# arm.net
KiCad netlist of a schematic drawn in Altium Designer
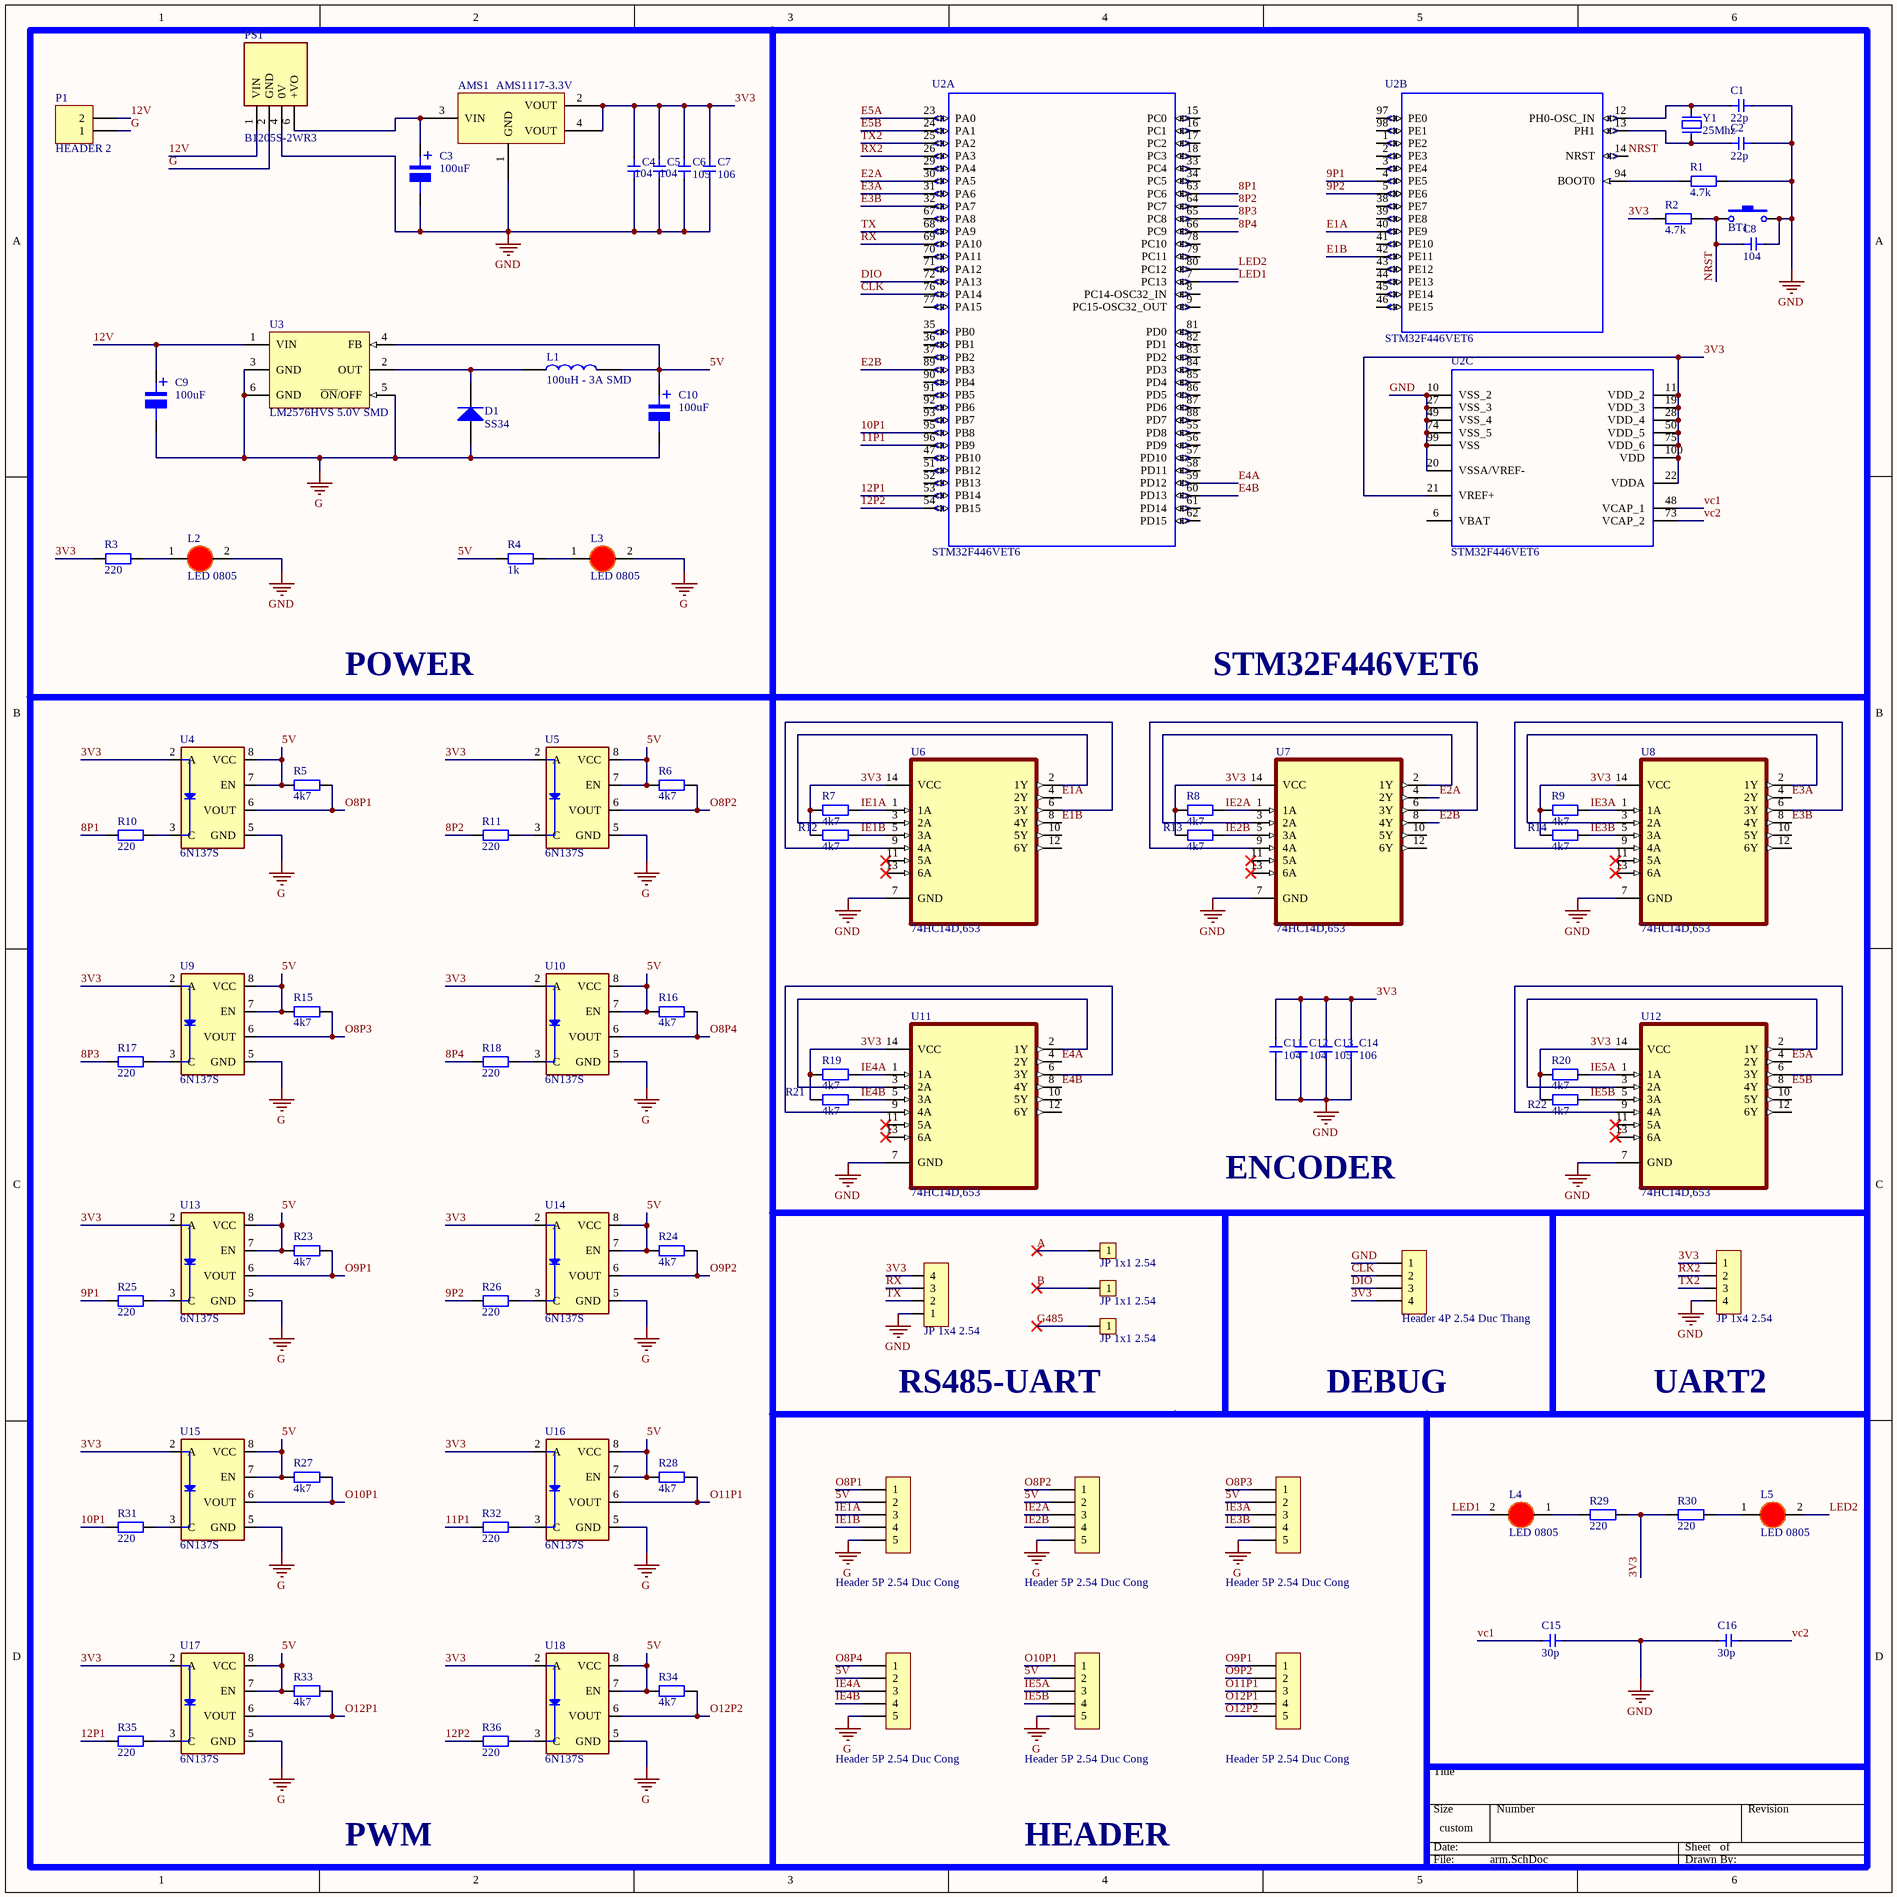
[diagram p0: arm.SchDoc]

(export (version "E")
  (design (tool "Eeschema 10.0.6"))
  (components
    (comp (ref "AMS1")
      (value "AMS1117-3.3V")
      (footprint "SOT223")
      (description "Dán")
      (libsource (lib "Altium_Lib_by_KhueNguyenCreator") (part "AMS1117 SMD"))
    )
    (comp (ref "BT1")
      (value "Nut Nhan 2 Chan SMD 3x6x2.5")
      (footprint "Nut Nhan 2 Chan SMD 3x6x2.5")
      (libsource (lib "Altium_Lib_by_KhueNguyenCreator") (part "Nut Nhan 2 Chan SMD 3x6x2.5"))
    )
    (comp (ref "C1")
      (value "22p")
      (footprint "Cap 0805")
      (description "Capacitor SMD 0805")
      (libsource (lib "Altium_Lib_by_KhueNguyenCreator") (part "Cap 0805"))
    )
    (comp (ref "C2")
      (value "22p")
      (footprint "Cap 0805")
      (description "Capacitor SMD 0805")
      (libsource (lib "Altium_Lib_by_KhueNguyenCreator") (part "Cap 0805"))
    )
    (comp (ref "C3")
      (value "100uF")
      (footprint "tu nhom 6.3 (d)")
      (description "Dán")
      (libsource (lib "Altium_Lib_by_KhueNguyenCreator") (part "Tu Nhom 100uF 16V"))
    )
    (comp (ref "C4")
      (value "104")
      (footprint "Cap 0805")
      (description "Capacitor SMD 0805")
      (libsource (lib "Altium_Lib_by_KhueNguyenCreator") (part "Cap 0805"))
    )
    (comp (ref "C5")
      (value "104")
      (footprint "Cap 0805")
      (description "Capacitor SMD 0805")
      (libsource (lib "Altium_Lib_by_KhueNguyenCreator") (part "Cap 0805"))
    )
    (comp (ref "C6")
      (value "105")
      (footprint "Cap 0805")
      (description "Capacitor SMD 0805")
      (libsource (lib "Altium_Lib_by_KhueNguyenCreator") (part "Cap 0805"))
    )
    (comp (ref "C7")
      (value "106")
      (footprint "Cap 0805")
      (description "Capacitor SMD 0805")
      (libsource (lib "Altium_Lib_by_KhueNguyenCreator") (part "Cap 0805"))
    )
    (comp (ref "C8")
      (value "104")
      (footprint "Cap 0805")
      (description "Capacitor SMD 0805")
      (libsource (lib "Altium_Lib_by_KhueNguyenCreator") (part "Cap 0805"))
    )
    (comp (ref "C9")
      (value "100uF")
      (footprint "tu nhom 6.3 (d)")
      (description "Dán")
      (libsource (lib "Altium_Lib_by_KhueNguyenCreator") (part "Tu Nhom 100uF 25V"))
    )
    (comp (ref "C10")
      (value "100uF")
      (footprint "tu nhom 6.3 (d)")
      (description "Dán")
      (libsource (lib "Altium_Lib_by_KhueNguyenCreator") (part "Tu Nhom 100uF 16V"))
    )
    (comp (ref "C11")
      (value "104")
      (footprint "Cap 0805")
      (description "Capacitor SMD 0805")
      (libsource (lib "Altium_Lib_by_KhueNguyenCreator") (part "Cap 0805"))
    )
    (comp (ref "C12")
      (value "104")
      (footprint "Cap 0805")
      (description "Capacitor SMD 0805")
      (libsource (lib "Altium_Lib_by_KhueNguyenCreator") (part "Cap 0805"))
    )
    (comp (ref "C13")
      (value "105")
      (footprint "Cap 0805")
      (description "Capacitor SMD 0805")
      (libsource (lib "Altium_Lib_by_KhueNguyenCreator") (part "Cap 0805"))
    )
    (comp (ref "C14")
      (value "106")
      (footprint "Cap 0805")
      (description "Capacitor SMD 0805")
      (libsource (lib "Altium_Lib_by_KhueNguyenCreator") (part "Cap 0805"))
    )
    (comp (ref "C15")
      (value "30p")
      (footprint "Cap 0805")
      (description "Capacitor SMD 0805")
      (libsource (lib "Altium_Lib_by_KhueNguyenCreator") (part "Cap 0805"))
    )
    (comp (ref "C16")
      (value "30p")
      (footprint "Cap 0805")
      (description "Capacitor SMD 0805")
      (libsource (lib "Altium_Lib_by_KhueNguyenCreator") (part "Cap 0805"))
    )
    (comp (ref "D1")
      (value "SS34")
      (footprint "DIODE SMA")
      (description "Dán")
      (libsource (lib "Altium_Lib_by_KhueNguyenCreator") (part "Diode SS34 ( 1N5822 )"))
    )
    (comp (ref "H1")
      (value "Header 4P 2.54 Duc Thang")
      (footprint "XH2.54M-4")
      (description "Cắm")
      (libsource (lib "Altium_Lib_by_KhueNguyenCreator") (part "Header 4P 2.54 Duc Thang"))
    )
    (comp (ref "H2")
      (value "Header 5P 2.54 Duc Cong")
      (footprint "Header 5P DC 2.54")
      (description "Cắm")
      (libsource (lib "Altium_Lib_by_KhueNguyenCreator") (part "Header 5P 2.54 Duc Cong"))
    )
    (comp (ref "H3")
      (value "Header 5P 2.54 Duc Cong")
      (footprint "Header 5P DC 2.54")
      (description "Cắm")
      (libsource (lib "Altium_Lib_by_KhueNguyenCreator") (part "Header 5P 2.54 Duc Cong"))
    )
    (comp (ref "H4")
      (value "Header 5P 2.54 Duc Cong")
      (footprint "Header 5P DC 2.54")
      (description "Cắm")
      (libsource (lib "Altium_Lib_by_KhueNguyenCreator") (part "Header 5P 2.54 Duc Cong"))
    )
    (comp (ref "H5")
      (value "Header 5P 2.54 Duc Cong")
      (footprint "Header 5P DC 2.54")
      (description "Cắm")
      (libsource (lib "Altium_Lib_by_KhueNguyenCreator") (part "Header 5P 2.54 Duc Cong"))
    )
    (comp (ref "H6")
      (value "Header 5P 2.54 Duc Cong")
      (footprint "Header 5P DC 2.54")
      (description "Cắm")
      (libsource (lib "Altium_Lib_by_KhueNguyenCreator") (part "Header 5P 2.54 Duc Cong"))
    )
    (comp (ref "H7")
      (value "Header 5P 2.54 Duc Cong")
      (footprint "Header 5P DC 2.54")
      (description "Cắm")
      (libsource (lib "Altium_Lib_by_KhueNguyenCreator") (part "Header 5P 2.54 Duc Cong"))
    )
    (comp (ref "JP1")
      (value "JP 1x1 2.54")
      (footprint "JP 1x1 DT")
      (description "Cắm")
      (libsource (lib "Altium_Lib_by_KhueNguyenCreator") (part "JP 1x1 2.54 Duc Cong"))
    )
    (comp (ref "JP2")
      (value "JP 1x4 2.54")
      (footprint "JP 1x4 DT")
      (description "Cắm")
      (libsource (lib "") (part "JP 1x4 2.54 Duc Thang_1"))
    )
    (comp (ref "JP3")
      (value "JP 1x4 2.54")
      (footprint "JP 1x4 DT")
      (description "Cắm")
      (libsource (lib "Altium_Lib_by_KhueNguyenCreator") (part "JP 1x4 2.54 Duc Thang"))
    )
    (comp (ref "JP4")
      (value "JP 1x1 2.54")
      (footprint "JP 1x1 DT")
      (description "Cắm")
      (libsource (lib "Altium_Lib_by_KhueNguyenCreator") (part "JP 1x1 2.54 Duc Cong"))
    )
    (comp (ref "JP5")
      (value "JP 1x1 2.54")
      (footprint "JP 1x1 DT")
      (description "Cắm")
      (libsource (lib "Altium_Lib_by_KhueNguyenCreator") (part "JP 1x1 2.54 Duc Cong"))
    )
    (comp (ref "L1")
      (value "100uH - 3A SMD")
      (footprint "Cuon Cam 12x12x10")
      (description "Dán")
      (libsource (lib "Altium_Lib_by_KhueNguyenCreator") (part "CUON CAM 100uH SMD"))
    )
    (comp (ref "L2")
      (value "LED 0805")
      (footprint "LED-0805-Red")
      (description "Dán")
      (libsource (lib "Altium_Lib_by_KhueNguyenCreator") (part "LED 0805 Do"))
    )
    (comp (ref "L3")
      (value "LED 0805")
      (footprint "LED-0805-Red")
      (description "Dán")
      (libsource (lib "Altium_Lib_by_KhueNguyenCreator") (part "LED 0805 Do"))
    )
    (comp (ref "L4")
      (value "LED 0805")
      (footprint "LED-0805-Red")
      (description "Dán")
      (libsource (lib "Altium_Lib_by_KhueNguyenCreator") (part "LED 0805 Do"))
    )
    (comp (ref "L5")
      (value "LED 0805")
      (footprint "LED-0805-Red")
      (description "Dán")
      (libsource (lib "Altium_Lib_by_KhueNguyenCreator") (part "LED 0805 Do"))
    )
    (comp (ref "P1")
      (value "HEADER 2")
      (footprint "CON 2")
      (libsource (lib "KhanhBK_Library_4") (part "HEADER 2"))
    )
    (comp (ref "PS1")
      (value "B1205S-2WR3")
      (footprint "SamacSys:B1205S2WR3")
      (description "Power Supply")
      (libsource (lib "*") (part "B1205S-2WR3"))
    )
    (comp (ref "R1")
      (value "4.7k")
      (footprint "tro smd 0805")
      (description "Dán")
      (libsource (lib "Altium_Lib_by_KhueNguyenCreator") (part "Tro 0805 1% 0.22R"))
    )
    (comp (ref "R2")
      (value "4.7k")
      (footprint "tro smd 0805")
      (description "Dán")
      (libsource (lib "Altium_Lib_by_KhueNguyenCreator") (part "Tro 0805 1% 0.22R"))
    )
    (comp (ref "R3")
      (value "220")
      (footprint "tro smd 0805")
      (description "Dán")
      (libsource (lib "Altium_Lib_by_KhueNguyenCreator") (part "Tro 0805 1% 0.22R"))
    )
    (comp (ref "R4")
      (value "1k")
      (footprint "tro smd 0805")
      (description "Dán")
      (libsource (lib "Altium_Lib_by_KhueNguyenCreator") (part "Tro 0805 1% 0.22R"))
    )
    (comp (ref "R5")
      (value "4k7")
      (footprint "tro smd 0805")
      (description "Dán")
      (libsource (lib "Altium_Lib_by_KhueNguyenCreator") (part "Tro 0805 1% 0.22R"))
    )
    (comp (ref "R6")
      (value "4k7")
      (footprint "tro smd 0805")
      (description "Dán")
      (libsource (lib "Altium_Lib_by_KhueNguyenCreator") (part "Tro 0805 1% 0.22R"))
    )
    (comp (ref "R7")
      (value "4k7")
      (footprint "tro smd 0805")
      (description "Dán")
      (libsource (lib "Altium_Lib_by_KhueNguyenCreator") (part "Tro 0805 1% 0.22R"))
    )
    (comp (ref "R8")
      (value "4k7")
      (footprint "tro smd 0805")
      (description "Dán")
      (libsource (lib "Altium_Lib_by_KhueNguyenCreator") (part "Tro 0805 1% 0.22R"))
    )
    (comp (ref "R9")
      (value "4k7")
      (footprint "tro smd 0805")
      (description "Dán")
      (libsource (lib "Altium_Lib_by_KhueNguyenCreator") (part "Tro 0805 1% 0.22R"))
    )
    (comp (ref "R10")
      (value "220")
      (footprint "tro smd 0805")
      (description "Dán")
      (libsource (lib "Altium_Lib_by_KhueNguyenCreator") (part "Tro 0805 1% 0.22R"))
    )
    (comp (ref "R11")
      (value "220")
      (footprint "tro smd 0805")
      (description "Dán")
      (libsource (lib "Altium_Lib_by_KhueNguyenCreator") (part "Tro 0805 1% 0.22R"))
    )
    (comp (ref "R12")
      (value "4k7")
      (footprint "tro smd 0805")
      (description "Dán")
      (libsource (lib "Altium_Lib_by_KhueNguyenCreator") (part "Tro 0805 1% 0.22R"))
    )
    (comp (ref "R13")
      (value "4k7")
      (footprint "tro smd 0805")
      (description "Dán")
      (libsource (lib "Altium_Lib_by_KhueNguyenCreator") (part "Tro 0805 1% 0.22R"))
    )
    (comp (ref "R14")
      (value "4k7")
      (footprint "tro smd 0805")
      (description "Dán")
      (libsource (lib "Altium_Lib_by_KhueNguyenCreator") (part "Tro 0805 1% 0.22R"))
    )
    (comp (ref "R15")
      (value "4k7")
      (footprint "tro smd 0805")
      (description "Dán")
      (libsource (lib "Altium_Lib_by_KhueNguyenCreator") (part "Tro 0805 1% 0.22R"))
    )
    (comp (ref "R16")
      (value "4k7")
      (footprint "tro smd 0805")
      (description "Dán")
      (libsource (lib "Altium_Lib_by_KhueNguyenCreator") (part "Tro 0805 1% 0.22R"))
    )
    (comp (ref "R17")
      (value "220")
      (footprint "tro smd 0805")
      (description "Dán")
      (libsource (lib "Altium_Lib_by_KhueNguyenCreator") (part "Tro 0805 1% 0.22R"))
    )
    (comp (ref "R18")
      (value "220")
      (footprint "tro smd 0805")
      (description "Dán")
      (libsource (lib "Altium_Lib_by_KhueNguyenCreator") (part "Tro 0805 1% 0.22R"))
    )
    (comp (ref "R19")
      (value "4k7")
      (footprint "tro smd 0805")
      (description "Dán")
      (libsource (lib "Altium_Lib_by_KhueNguyenCreator") (part "Tro 0805 1% 0.22R"))
    )
    (comp (ref "R20")
      (value "4k7")
      (footprint "tro smd 0805")
      (description "Dán")
      (libsource (lib "Altium_Lib_by_KhueNguyenCreator") (part "Tro 0805 1% 0.22R"))
    )
    (comp (ref "R21")
      (value "4k7")
      (footprint "tro smd 0805")
      (description "Dán")
      (libsource (lib "Altium_Lib_by_KhueNguyenCreator") (part "Tro 0805 1% 0.22R"))
    )
    (comp (ref "R22")
      (value "4k7")
      (footprint "tro smd 0805")
      (description "Dán")
      (libsource (lib "Altium_Lib_by_KhueNguyenCreator") (part "Tro 0805 1% 0.22R"))
    )
    (comp (ref "R23")
      (value "4k7")
      (footprint "tro smd 0805")
      (description "Dán")
      (libsource (lib "Altium_Lib_by_KhueNguyenCreator") (part "Tro 0805 1% 0.22R"))
    )
    (comp (ref "R24")
      (value "4k7")
      (footprint "tro smd 0805")
      (description "Dán")
      (libsource (lib "Altium_Lib_by_KhueNguyenCreator") (part "Tro 0805 1% 0.22R"))
    )
    (comp (ref "R25")
      (value "220")
      (footprint "tro smd 0805")
      (description "Dán")
      (libsource (lib "Altium_Lib_by_KhueNguyenCreator") (part "Tro 0805 1% 0.22R"))
    )
    (comp (ref "R26")
      (value "220")
      (footprint "tro smd 0805")
      (description "Dán")
      (libsource (lib "Altium_Lib_by_KhueNguyenCreator") (part "Tro 0805 1% 0.22R"))
    )
    (comp (ref "R27")
      (value "4k7")
      (footprint "tro smd 0805")
      (description "Dán")
      (libsource (lib "Altium_Lib_by_KhueNguyenCreator") (part "Tro 0805 1% 0.22R"))
    )
    (comp (ref "R28")
      (value "4k7")
      (footprint "tro smd 0805")
      (description "Dán")
      (libsource (lib "Altium_Lib_by_KhueNguyenCreator") (part "Tro 0805 1% 0.22R"))
    )
    (comp (ref "R29")
      (value "220")
      (footprint "tro smd 0805")
      (description "Dán")
      (libsource (lib "Altium_Lib_by_KhueNguyenCreator") (part "Tro 0805 1% 0.22R"))
    )
    (comp (ref "R30")
      (value "220")
      (footprint "tro smd 0805")
      (description "Dán")
      (libsource (lib "Altium_Lib_by_KhueNguyenCreator") (part "Tro 0805 1% 0.22R"))
    )
    (comp (ref "R31")
      (value "220")
      (footprint "tro smd 0805")
      (description "Dán")
      (libsource (lib "Altium_Lib_by_KhueNguyenCreator") (part "Tro 0805 1% 0.22R"))
    )
    (comp (ref "R32")
      (value "220")
      (footprint "tro smd 0805")
      (description "Dán")
      (libsource (lib "Altium_Lib_by_KhueNguyenCreator") (part "Tro 0805 1% 0.22R"))
    )
    (comp (ref "R33")
      (value "4k7")
      (footprint "tro smd 0805")
      (description "Dán")
      (libsource (lib "Altium_Lib_by_KhueNguyenCreator") (part "Tro 0805 1% 0.22R"))
    )
    (comp (ref "R34")
      (value "4k7")
      (footprint "tro smd 0805")
      (description "Dán")
      (libsource (lib "Altium_Lib_by_KhueNguyenCreator") (part "Tro 0805 1% 0.22R"))
    )
    (comp (ref "R35")
      (value "220")
      (footprint "tro smd 0805")
      (description "Dán")
      (libsource (lib "Altium_Lib_by_KhueNguyenCreator") (part "Tro 0805 1% 0.22R"))
    )
    (comp (ref "R36")
      (value "220")
      (footprint "tro smd 0805")
      (description "Dán")
      (libsource (lib "Altium_Lib_by_KhueNguyenCreator") (part "Tro 0805 1% 0.22R"))
    )
    (comp (ref "U2")
      (value "STM32F446VET6")
      (footprint "LQFP100-14X14MM")
      (fields (field (name "MF") "STMicroelectronics"))
      (libsource (lib "STM32F446VET6") (part "STM32F446VET6"))
    )
    (comp (ref "U3")
      (value "LM2576HVS 5.0V SMD")
      (footprint "TO263-5")
      (description "Dán")
      (libsource (lib "Altium_Lib_by_KhueNguyenCreator") (part "LM2576HVS 5.0V SMD"))
    )
    (comp (ref "U4")
      (value "6N137S")
      (footprint "8-SMD")
      (description "Logic Output Optoisolator 15MBd Open Collector 5000Vrms 1 Channel 10kV/Âµs CMTI 8-SMD")
      (fields (field (name "MF") "Lite-On Inc."))
      (libsource (lib "6N137S") (part "6N137S"))
    )
    (comp (ref "U5")
      (value "6N137S")
      (footprint "8-SMD")
      (description "Logic Output Optoisolator 15MBd Open Collector 5000Vrms 1 Channel 10kV/Âµs CMTI 8-SMD")
      (fields (field (name "MF") "Lite-On Inc."))
      (libsource (lib "6N137S") (part "6N137S"))
    )
    (comp (ref "U6")
      (value "74HC14D,653")
      (footprint "SOIC127P600X175-14N")
      (description "Inverter IC 6 Channel Schmitt Trigger 14-SO")
      (fields (field (name "MF") "Nexperia USA"))
      (libsource (lib "74HC14D_653") (part "74HC14D,653"))
    )
    (comp (ref "U7")
      (value "74HC14D,653")
      (footprint "SOIC127P600X175-14N")
      (description "Inverter IC 6 Channel Schmitt Trigger 14-SO")
      (fields (field (name "MF") "Nexperia USA"))
      (libsource (lib "74HC14D_653") (part "74HC14D,653"))
    )
    (comp (ref "U8")
      (value "74HC14D,653")
      (footprint "SOIC127P600X175-14N")
      (description "Inverter IC 6 Channel Schmitt Trigger 14-SO")
      (fields (field (name "MF") "Nexperia USA"))
      (libsource (lib "74HC14D_653") (part "74HC14D,653"))
    )
    (comp (ref "U9")
      (value "6N137S")
      (footprint "8-SMD")
      (description "Logic Output Optoisolator 15MBd Open Collector 5000Vrms 1 Channel 10kV/Âµs CMTI 8-SMD")
      (fields (field (name "MF") "Lite-On Inc."))
      (libsource (lib "6N137S") (part "6N137S"))
    )
    (comp (ref "U10")
      (value "6N137S")
      (footprint "8-SMD")
      (description "Logic Output Optoisolator 15MBd Open Collector 5000Vrms 1 Channel 10kV/Âµs CMTI 8-SMD")
      (fields (field (name "MF") "Lite-On Inc."))
      (libsource (lib "6N137S") (part "6N137S"))
    )
    (comp (ref "U11")
      (value "74HC14D,653")
      (footprint "SOIC127P600X175-14N")
      (description "Inverter IC 6 Channel Schmitt Trigger 14-SO")
      (fields (field (name "MF") "Nexperia USA"))
      (libsource (lib "74HC14D_653") (part "74HC14D,653"))
    )
    (comp (ref "U12")
      (value "74HC14D,653")
      (footprint "SOIC127P600X175-14N")
      (description "Inverter IC 6 Channel Schmitt Trigger 14-SO")
      (fields (field (name "MF") "Nexperia USA"))
      (libsource (lib "74HC14D_653") (part "74HC14D,653"))
    )
    (comp (ref "U13")
      (value "6N137S")
      (footprint "8-SMD")
      (description "Logic Output Optoisolator 15MBd Open Collector 5000Vrms 1 Channel 10kV/Âµs CMTI 8-SMD")
      (fields (field (name "MF") "Lite-On Inc."))
      (libsource (lib "6N137S") (part "6N137S"))
    )
    (comp (ref "U14")
      (value "6N137S")
      (footprint "8-SMD")
      (description "Logic Output Optoisolator 15MBd Open Collector 5000Vrms 1 Channel 10kV/Âµs CMTI 8-SMD")
      (fields (field (name "MF") "Lite-On Inc."))
      (libsource (lib "6N137S") (part "6N137S"))
    )
    (comp (ref "U15")
      (value "6N137S")
      (footprint "8-SMD")
      (description "Logic Output Optoisolator 15MBd Open Collector 5000Vrms 1 Channel 10kV/Âµs CMTI 8-SMD")
      (fields (field (name "MF") "Lite-On Inc."))
      (libsource (lib "6N137S") (part "6N137S"))
    )
    (comp (ref "U16")
      (value "6N137S")
      (footprint "8-SMD")
      (description "Logic Output Optoisolator 15MBd Open Collector 5000Vrms 1 Channel 10kV/Âµs CMTI 8-SMD")
      (fields (field (name "MF") "Lite-On Inc."))
      (libsource (lib "6N137S") (part "6N137S"))
    )
    (comp (ref "U17")
      (value "6N137S")
      (footprint "8-SMD")
      (description "Logic Output Optoisolator 15MBd Open Collector 5000Vrms 1 Channel 10kV/Âµs CMTI 8-SMD")
      (fields (field (name "MF") "Lite-On Inc."))
      (libsource (lib "6N137S") (part "6N137S"))
    )
    (comp (ref "U18")
      (value "6N137S")
      (footprint "8-SMD")
      (description "Logic Output Optoisolator 15MBd Open Collector 5000Vrms 1 Channel 10kV/Âµs CMTI 8-SMD")
      (fields (field (name "MF") "Lite-On Inc."))
      (libsource (lib "6N137S") (part "6N137S"))
    )
    (comp (ref "Y1")
      (value "25Mhz")
      (footprint "Thach Anh 2 chan cam")
      (description "Crystal For all Crystal 2pin.")
      (libsource (lib "Altium_Lib_by_KhueNguyenCreator") (part "Thach Anh 2 chan Cam"))
    )
  )
  (nets
    (net (code "1") (name "/3V3") (class "Default")
      (node (ref "AMS1") (pin "2") (pinfunction "VOUT_2") (pintype "passive"))
      (node (ref "AMS1") (pin "4") (pinfunction "VOUT_4") (pintype "passive"))
      (node (ref "C11") (pin "1") (pinfunction "1_1") (pintype "passive"))
      (node (ref "C12") (pin "1") (pinfunction "1_1") (pintype "passive"))
      (node (ref "C13") (pin "1") (pinfunction "1_1") (pintype "passive"))
      (node (ref "C14") (pin "1") (pinfunction "1_1") (pintype "passive"))
      (node (ref "C4") (pin "1") (pinfunction "1_1") (pintype "passive"))
      (node (ref "C5") (pin "1") (pinfunction "1_1") (pintype "passive"))
      (node (ref "C6") (pin "1") (pinfunction "1_1") (pintype "passive"))
      (node (ref "C7") (pin "1") (pinfunction "1_1") (pintype "passive"))
      (node (ref "H1") (pin "4") (pinfunction "4_4") (pintype "passive"))
      (node (ref "JP2") (pin "4") (pinfunction "4_4") (pintype "passive"))
      (node (ref "JP3") (pin "1") (pinfunction "1_1") (pintype "passive"))
      (node (ref "R12") (pin "1") (pinfunction "1_1") (pintype "passive"))
      (node (ref "R13") (pin "1") (pinfunction "1_1") (pintype "passive"))
      (node (ref "R14") (pin "1") (pinfunction "1_1") (pintype "passive"))
      (node (ref "R19") (pin "1") (pinfunction "1_1") (pintype "passive"))
      (node (ref "R2") (pin "2") (pinfunction "2_2") (pintype "passive"))
      (node (ref "R20") (pin "1") (pinfunction "1_1") (pintype "passive"))
      (node (ref "R21") (pin "1") (pinfunction "1_1") (pintype "passive"))
      (node (ref "R22") (pin "1") (pinfunction "1_1") (pintype "passive"))
      (node (ref "R29") (pin "2") (pinfunction "2_2") (pintype "passive"))
      (node (ref "R3") (pin "1") (pinfunction "1_1") (pintype "passive"))
      (node (ref "R30") (pin "1") (pinfunction "1_1") (pintype "passive"))
      (node (ref "R7") (pin "1") (pinfunction "1_1") (pintype "passive"))
      (node (ref "R8") (pin "1") (pinfunction "1_1") (pintype "passive"))
      (node (ref "R9") (pin "1") (pinfunction "1_1") (pintype "passive"))
      (node (ref "U10") (pin "2") (pinfunction "A_2") (pintype "bidirectional"))
      (node (ref "U11") (pin "14") (pinfunction "VCC_14") (pintype "power_in"))
      (node (ref "U12") (pin "14") (pinfunction "VCC_14") (pintype "power_in"))
      (node (ref "U13") (pin "2") (pinfunction "A_2") (pintype "bidirectional"))
      (node (ref "U14") (pin "2") (pinfunction "A_2") (pintype "bidirectional"))
      (node (ref "U15") (pin "2") (pinfunction "A_2") (pintype "bidirectional"))
      (node (ref "U16") (pin "2") (pinfunction "A_2") (pintype "bidirectional"))
      (node (ref "U17") (pin "2") (pinfunction "A_2") (pintype "bidirectional"))
      (node (ref "U18") (pin "2") (pinfunction "A_2") (pintype "bidirectional"))
      (node (ref "U2") (pin "100") (pinfunction "VDD_100") (pintype "power_in"))
      (node (ref "U2") (pin "11") (pinfunction "VDD_2_11") (pintype "power_in"))
      (node (ref "U2") (pin "19") (pinfunction "VDD_3_19") (pintype "power_in"))
      (node (ref "U2") (pin "21") (pinfunction "VREF+_21") (pintype "power_in"))
      (node (ref "U2") (pin "22") (pinfunction "VDDA_22") (pintype "power_in"))
      (node (ref "U2") (pin "28") (pinfunction "VDD_4_28") (pintype "power_in"))
      (node (ref "U2") (pin "50") (pinfunction "VDD_5_50") (pintype "power_in"))
      (node (ref "U2") (pin "75") (pinfunction "VDD_6_75") (pintype "power_in"))
      (node (ref "U4") (pin "2") (pinfunction "A_2") (pintype "bidirectional"))
      (node (ref "U5") (pin "2") (pinfunction "A_2") (pintype "bidirectional"))
      (node (ref "U6") (pin "14") (pinfunction "VCC_14") (pintype "power_in"))
      (node (ref "U7") (pin "14") (pinfunction "VCC_14") (pintype "power_in"))
      (node (ref "U8") (pin "14") (pinfunction "VCC_14") (pintype "power_in"))
      (node (ref "U9") (pin "2") (pinfunction "A_2") (pintype "bidirectional"))
    )
    (net (code "2") (name "/5V") (class "Default")
      (node (ref "C10") (pin "1") (pinfunction "1_1") (pintype "passive"))
      (node (ref "H2") (pin "2") (pinfunction "2_2") (pintype "passive"))
      (node (ref "H3") (pin "2") (pinfunction "2_2") (pintype "passive"))
      (node (ref "H4") (pin "2") (pinfunction "2_2") (pintype "passive"))
      (node (ref "H5") (pin "2") (pinfunction "2_2") (pintype "passive"))
      (node (ref "H6") (pin "2") (pinfunction "2_2") (pintype "passive"))
      (node (ref "L1") (pin "2") (pinfunction "2_2") (pintype "passive"))
      (node (ref "R15") (pin "1") (pinfunction "1_1") (pintype "passive"))
      (node (ref "R16") (pin "1") (pinfunction "1_1") (pintype "passive"))
      (node (ref "R23") (pin "1") (pinfunction "1_1") (pintype "passive"))
      (node (ref "R24") (pin "1") (pinfunction "1_1") (pintype "passive"))
      (node (ref "R27") (pin "1") (pinfunction "1_1") (pintype "passive"))
      (node (ref "R28") (pin "1") (pinfunction "1_1") (pintype "passive"))
      (node (ref "R33") (pin "1") (pinfunction "1_1") (pintype "passive"))
      (node (ref "R34") (pin "1") (pinfunction "1_1") (pintype "passive"))
      (node (ref "R4") (pin "1") (pinfunction "1_1") (pintype "passive"))
      (node (ref "R5") (pin "1") (pinfunction "1_1") (pintype "passive"))
      (node (ref "R6") (pin "1") (pinfunction "1_1") (pintype "passive"))
      (node (ref "U10") (pin "7") (pinfunction "EN_7") (pintype "bidirectional"))
      (node (ref "U10") (pin "8") (pinfunction "VCC_8") (pintype "bidirectional"))
      (node (ref "U13") (pin "7") (pinfunction "EN_7") (pintype "bidirectional"))
      (node (ref "U13") (pin "8") (pinfunction "VCC_8") (pintype "bidirectional"))
      (node (ref "U14") (pin "7") (pinfunction "EN_7") (pintype "bidirectional"))
      (node (ref "U14") (pin "8") (pinfunction "VCC_8") (pintype "bidirectional"))
      (node (ref "U15") (pin "7") (pinfunction "EN_7") (pintype "bidirectional"))
      (node (ref "U15") (pin "8") (pinfunction "VCC_8") (pintype "bidirectional"))
      (node (ref "U16") (pin "7") (pinfunction "EN_7") (pintype "bidirectional"))
      (node (ref "U16") (pin "8") (pinfunction "VCC_8") (pintype "bidirectional"))
      (node (ref "U17") (pin "7") (pinfunction "EN_7") (pintype "bidirectional"))
      (node (ref "U17") (pin "8") (pinfunction "VCC_8") (pintype "bidirectional"))
      (node (ref "U18") (pin "7") (pinfunction "EN_7") (pintype "bidirectional"))
      (node (ref "U18") (pin "8") (pinfunction "VCC_8") (pintype "bidirectional"))
      (node (ref "U3") (pin "4") (pinfunction "FB_4") (pintype "input"))
      (node (ref "U4") (pin "7") (pinfunction "EN_7") (pintype "bidirectional"))
      (node (ref "U4") (pin "8") (pinfunction "VCC_8") (pintype "bidirectional"))
      (node (ref "U5") (pin "7") (pinfunction "EN_7") (pintype "bidirectional"))
      (node (ref "U5") (pin "8") (pinfunction "VCC_8") (pintype "bidirectional"))
      (node (ref "U9") (pin "7") (pinfunction "EN_7") (pintype "bidirectional"))
      (node (ref "U9") (pin "8") (pinfunction "VCC_8") (pintype "bidirectional"))
    )
    (net (code "3") (name "/8P1") (class "Default")
      (node (ref "R10") (pin "1") (pinfunction "1_1") (pintype "passive"))
      (node (ref "U2") (pin "63") (pinfunction "PC6_63") (pintype "bidirectional"))
    )
    (net (code "4") (name "/8P2") (class "Default")
      (node (ref "R11") (pin "1") (pinfunction "1_1") (pintype "passive"))
      (node (ref "U2") (pin "64") (pinfunction "PC7_64") (pintype "bidirectional"))
    )
    (net (code "5") (name "/8P3") (class "Default")
      (node (ref "R17") (pin "1") (pinfunction "1_1") (pintype "passive"))
      (node (ref "U2") (pin "65") (pinfunction "PC8_65") (pintype "bidirectional"))
    )
    (net (code "6") (name "/8P4") (class "Default")
      (node (ref "R18") (pin "1") (pinfunction "1_1") (pintype "passive"))
      (node (ref "U2") (pin "66") (pinfunction "PC9_66") (pintype "bidirectional"))
    )
    (net (code "7") (name "/9P1") (class "Default")
      (node (ref "R25") (pin "1") (pinfunction "1_1") (pintype "passive"))
      (node (ref "U2") (pin "4") (pinfunction "PE5_4") (pintype "bidirectional"))
    )
    (net (code "8") (name "/9P2") (class "Default")
      (node (ref "R26") (pin "1") (pinfunction "1_1") (pintype "passive"))
      (node (ref "U2") (pin "5") (pinfunction "PE6_5") (pintype "bidirectional"))
    )
    (net (code "9") (name "/10P1") (class "Default")
      (node (ref "R31") (pin "1") (pinfunction "1_1") (pintype "passive"))
      (node (ref "U2") (pin "95") (pinfunction "PB8_95") (pintype "bidirectional"))
    )
    (net (code "10") (name "/11P1") (class "Default")
      (node (ref "R32") (pin "1") (pinfunction "1_1") (pintype "passive"))
      (node (ref "U2") (pin "96") (pinfunction "PB9_96") (pintype "bidirectional"))
    )
    (net (code "11") (name "/12P1") (class "Default")
      (node (ref "R35") (pin "1") (pinfunction "1_1") (pintype "passive"))
      (node (ref "U2") (pin "53") (pinfunction "PB14_53") (pintype "bidirectional"))
    )
    (net (code "12") (name "/12P2") (class "Default")
      (node (ref "R36") (pin "1") (pinfunction "1_1") (pintype "passive"))
      (node (ref "U2") (pin "54") (pinfunction "PB15_54") (pintype "bidirectional"))
    )
    (net (code "13") (name "/12V") (class "Default")
      (node (ref "C9") (pin "1") (pinfunction "1_1") (pintype "passive"))
      (node (ref "P1") (pin "2") (pinfunction "2_2") (pintype "passive"))
      (node (ref "PS1") (pin "1") (pinfunction "VIN_1") (pintype "passive"))
      (node (ref "U3") (pin "1") (pinfunction "VIN_1") (pintype "power_in"))
    )
    (net (code "14") (name "/A") (class "Default")
      (node (ref "JP1") (pin "1") (pinfunction "1_1") (pintype "passive+no_connect"))
    )
    (net (code "15") (name "/B") (class "Default")
      (node (ref "JP4") (pin "1") (pinfunction "1_1") (pintype "passive+no_connect"))
    )
    (net (code "16") (name "/CLK") (class "Default")
      (node (ref "H1") (pin "2") (pinfunction "2_2") (pintype "passive"))
      (node (ref "U2") (pin "76") (pinfunction "PA14_76") (pintype "bidirectional"))
    )
    (net (code "17") (name "/DIO") (class "Default")
      (node (ref "H1") (pin "3") (pinfunction "3_3") (pintype "passive"))
      (node (ref "U2") (pin "72") (pinfunction "PA13_72") (pintype "bidirectional"))
    )
    (net (code "18") (name "/E1A") (class "Default")
      (node (ref "U2") (pin "40") (pinfunction "PE9_40") (pintype "bidirectional"))
      (node (ref "U6") (pin "4") (pinfunction "2Y_4") (pintype "output"))
    )
    (net (code "19") (name "/E1B") (class "Default")
      (node (ref "U2") (pin "42") (pinfunction "PE11_42") (pintype "bidirectional"))
      (node (ref "U6") (pin "8") (pinfunction "4Y_8") (pintype "output"))
    )
    (net (code "20") (name "/E2A") (class "Default")
      (node (ref "U2") (pin "30") (pinfunction "PA5_30") (pintype "bidirectional"))
      (node (ref "U7") (pin "4") (pinfunction "2Y_4") (pintype "output"))
    )
    (net (code "21") (name "/E2B") (class "Default")
      (node (ref "U2") (pin "89") (pinfunction "PB3_89") (pintype "bidirectional"))
      (node (ref "U7") (pin "8") (pinfunction "4Y_8") (pintype "output"))
    )
    (net (code "22") (name "/E3A") (class "Default")
      (node (ref "U2") (pin "31") (pinfunction "PA6_31") (pintype "bidirectional"))
      (node (ref "U8") (pin "4") (pinfunction "2Y_4") (pintype "output"))
    )
    (net (code "23") (name "/E3B") (class "Default")
      (node (ref "U2") (pin "32") (pinfunction "PA7_32") (pintype "bidirectional"))
      (node (ref "U8") (pin "8") (pinfunction "4Y_8") (pintype "output"))
    )
    (net (code "24") (name "/E4A") (class "Default")
      (node (ref "U11") (pin "4") (pinfunction "2Y_4") (pintype "output"))
      (node (ref "U2") (pin "59") (pinfunction "PD12_59") (pintype "bidirectional"))
    )
    (net (code "25") (name "/E4B") (class "Default")
      (node (ref "U11") (pin "8") (pinfunction "4Y_8") (pintype "output"))
      (node (ref "U2") (pin "60") (pinfunction "PD13_60") (pintype "bidirectional"))
    )
    (net (code "26") (name "/E5A") (class "Default")
      (node (ref "U12") (pin "4") (pinfunction "2Y_4") (pintype "output"))
      (node (ref "U2") (pin "23") (pinfunction "PA0_23") (pintype "bidirectional"))
    )
    (net (code "27") (name "/E5B") (class "Default")
      (node (ref "U12") (pin "8") (pinfunction "4Y_8") (pintype "output"))
      (node (ref "U2") (pin "24") (pinfunction "PA1_24") (pintype "bidirectional"))
    )
    (net (code "28") (name "/G485") (class "Default")
      (node (ref "JP5") (pin "1") (pinfunction "1_1") (pintype "passive+no_connect"))
    )
    (net (code "29") (name "/IE1A") (class "Default")
      (node (ref "H2") (pin "3") (pinfunction "3_3") (pintype "passive"))
      (node (ref "R7") (pin "2") (pinfunction "2_2") (pintype "passive"))
      (node (ref "U6") (pin "1") (pinfunction "1A_1") (pintype "input"))
    )
    (net (code "30") (name "/IE1B") (class "Default")
      (node (ref "H2") (pin "4") (pinfunction "4_4") (pintype "passive"))
      (node (ref "R12") (pin "2") (pinfunction "2_2") (pintype "passive"))
      (node (ref "U6") (pin "5") (pinfunction "3A_5") (pintype "input"))
    )
    (net (code "31") (name "/IE2A") (class "Default")
      (node (ref "H3") (pin "3") (pinfunction "3_3") (pintype "passive"))
      (node (ref "R8") (pin "2") (pinfunction "2_2") (pintype "passive"))
      (node (ref "U7") (pin "1") (pinfunction "1A_1") (pintype "input"))
    )
    (net (code "32") (name "/IE2B") (class "Default")
      (node (ref "H3") (pin "4") (pinfunction "4_4") (pintype "passive"))
      (node (ref "R13") (pin "2") (pinfunction "2_2") (pintype "passive"))
      (node (ref "U7") (pin "5") (pinfunction "3A_5") (pintype "input"))
    )
    (net (code "33") (name "/IE3A") (class "Default")
      (node (ref "H4") (pin "3") (pinfunction "3_3") (pintype "passive"))
      (node (ref "R9") (pin "2") (pinfunction "2_2") (pintype "passive"))
      (node (ref "U8") (pin "1") (pinfunction "1A_1") (pintype "input"))
    )
    (net (code "34") (name "/IE3B") (class "Default")
      (node (ref "H4") (pin "4") (pinfunction "4_4") (pintype "passive"))
      (node (ref "R14") (pin "2") (pinfunction "2_2") (pintype "passive"))
      (node (ref "U8") (pin "5") (pinfunction "3A_5") (pintype "input"))
    )
    (net (code "35") (name "/IE4A") (class "Default")
      (node (ref "H5") (pin "3") (pinfunction "3_3") (pintype "passive"))
      (node (ref "R19") (pin "2") (pinfunction "2_2") (pintype "passive"))
      (node (ref "U11") (pin "1") (pinfunction "1A_1") (pintype "input"))
    )
    (net (code "36") (name "/IE4B") (class "Default")
      (node (ref "H5") (pin "4") (pinfunction "4_4") (pintype "passive"))
      (node (ref "R21") (pin "2") (pinfunction "2_2") (pintype "passive"))
      (node (ref "U11") (pin "5") (pinfunction "3A_5") (pintype "input"))
    )
    (net (code "37") (name "/IE5A") (class "Default")
      (node (ref "H6") (pin "3") (pinfunction "3_3") (pintype "passive"))
      (node (ref "R20") (pin "2") (pinfunction "2_2") (pintype "passive"))
      (node (ref "U12") (pin "1") (pinfunction "1A_1") (pintype "input"))
    )
    (net (code "38") (name "/IE5B") (class "Default")
      (node (ref "H6") (pin "4") (pinfunction "4_4") (pintype "passive"))
      (node (ref "R22") (pin "2") (pinfunction "2_2") (pintype "passive"))
      (node (ref "U12") (pin "5") (pinfunction "3A_5") (pintype "input"))
    )
    (net (code "39") (name "/LED1") (class "Default")
      (node (ref "L4") (pin "2") (pinfunction "K_2") (pintype "passive"))
      (node (ref "U2") (pin "7") (pinfunction "PC13_7") (pintype "bidirectional"))
    )
    (net (code "40") (name "/LED2") (class "Default")
      (node (ref "L5") (pin "2") (pinfunction "K_2") (pintype "passive"))
      (node (ref "U2") (pin "80") (pinfunction "PC12_80") (pintype "bidirectional"))
    )
    (net (code "41") (name "/NRST") (class "Default")
      (node (ref "BT1") (pin "1") (pinfunction "1_1") (pintype "passive"))
      (node (ref "C8") (pin "1") (pinfunction "1_1") (pintype "passive"))
      (node (ref "R2") (pin "1") (pinfunction "1_1") (pintype "passive"))
      (node (ref "U2") (pin "14") (pinfunction "NRST_14") (pintype "bidirectional"))
    )
    (net (code "42") (name "/O8P1") (class "Default")
      (node (ref "H2") (pin "1") (pinfunction "1_1") (pintype "passive"))
      (node (ref "R5") (pin "2") (pinfunction "2_2") (pintype "passive"))
      (node (ref "U4") (pin "6") (pinfunction "VOUT_6") (pintype "bidirectional"))
    )
    (net (code "43") (name "/O8P2") (class "Default")
      (node (ref "H3") (pin "1") (pinfunction "1_1") (pintype "passive"))
      (node (ref "R6") (pin "2") (pinfunction "2_2") (pintype "passive"))
      (node (ref "U5") (pin "6") (pinfunction "VOUT_6") (pintype "bidirectional"))
    )
    (net (code "44") (name "/O8P3") (class "Default")
      (node (ref "H4") (pin "1") (pinfunction "1_1") (pintype "passive"))
      (node (ref "R15") (pin "2") (pinfunction "2_2") (pintype "passive"))
      (node (ref "U9") (pin "6") (pinfunction "VOUT_6") (pintype "bidirectional"))
    )
    (net (code "45") (name "/O8P4") (class "Default")
      (node (ref "H5") (pin "1") (pinfunction "1_1") (pintype "passive"))
      (node (ref "R16") (pin "2") (pinfunction "2_2") (pintype "passive"))
      (node (ref "U10") (pin "6") (pinfunction "VOUT_6") (pintype "bidirectional"))
    )
    (net (code "46") (name "/O9P1") (class "Default")
      (node (ref "H7") (pin "1") (pinfunction "1_1") (pintype "passive"))
      (node (ref "R23") (pin "2") (pinfunction "2_2") (pintype "passive"))
      (node (ref "U13") (pin "6") (pinfunction "VOUT_6") (pintype "bidirectional"))
    )
    (net (code "47") (name "/O9P2") (class "Default")
      (node (ref "H7") (pin "2") (pinfunction "2_2") (pintype "passive"))
      (node (ref "R24") (pin "2") (pinfunction "2_2") (pintype "passive"))
      (node (ref "U14") (pin "6") (pinfunction "VOUT_6") (pintype "bidirectional"))
    )
    (net (code "48") (name "/O10P1") (class "Default")
      (node (ref "H6") (pin "1") (pinfunction "1_1") (pintype "passive"))
      (node (ref "R27") (pin "2") (pinfunction "2_2") (pintype "passive"))
      (node (ref "U15") (pin "6") (pinfunction "VOUT_6") (pintype "bidirectional"))
    )
    (net (code "49") (name "/O11P1") (class "Default")
      (node (ref "H7") (pin "3") (pinfunction "3_3") (pintype "passive"))
      (node (ref "R28") (pin "2") (pinfunction "2_2") (pintype "passive"))
      (node (ref "U16") (pin "6") (pinfunction "VOUT_6") (pintype "bidirectional"))
    )
    (net (code "50") (name "/O12P1") (class "Default")
      (node (ref "H7") (pin "4") (pinfunction "4_4") (pintype "passive"))
      (node (ref "R33") (pin "2") (pinfunction "2_2") (pintype "passive"))
      (node (ref "U17") (pin "6") (pinfunction "VOUT_6") (pintype "bidirectional"))
    )
    (net (code "51") (name "/O12P2") (class "Default")
      (node (ref "H7") (pin "5") (pinfunction "5_5") (pintype "passive"))
      (node (ref "R34") (pin "2") (pinfunction "2_2") (pintype "passive"))
      (node (ref "U18") (pin "6") (pinfunction "VOUT_6") (pintype "bidirectional"))
    )
    (net (code "52") (name "/RX") (class "Default")
      (node (ref "JP2") (pin "3") (pinfunction "3_3") (pintype "passive"))
      (node (ref "U2") (pin "69") (pinfunction "PA10_69") (pintype "bidirectional"))
    )
    (net (code "53") (name "/RX2") (class "Default")
      (node (ref "JP3") (pin "2") (pinfunction "2_2") (pintype "passive"))
      (node (ref "U2") (pin "26") (pinfunction "PA3_26") (pintype "bidirectional"))
    )
    (net (code "54") (name "/TX") (class "Default")
      (node (ref "JP2") (pin "2") (pinfunction "2_2") (pintype "passive"))
      (node (ref "U2") (pin "68") (pinfunction "PA9_68") (pintype "bidirectional"))
    )
    (net (code "55") (name "/TX2") (class "Default")
      (node (ref "JP3") (pin "3") (pinfunction "3_3") (pintype "passive"))
      (node (ref "U2") (pin "25") (pinfunction "PA2_25") (pintype "bidirectional"))
    )
    (net (code "56") (name "/vc1") (class "Default")
      (node (ref "C15") (pin "1") (pinfunction "1_1") (pintype "passive"))
      (node (ref "U2") (pin "48") (pinfunction "VCAP_1_48") (pintype "power_in"))
    )
    (net (code "57") (name "/vc2") (class "Default")
      (node (ref "C16") (pin "2") (pinfunction "2_2") (pintype "passive"))
      (node (ref "U2") (pin "73") (pinfunction "VCAP_2_73") (pintype "power_in"))
    )
    (net (code "58") (name "G") (class "Default")
      (node (ref "C10") (pin "2") (pinfunction "2_2") (pintype "passive"))
      (node (ref "C9") (pin "2") (pinfunction "2_2") (pintype "passive"))
      (node (ref "D1") (pin "1") (pinfunction "A_1") (pintype "passive"))
      (node (ref "H2") (pin "5") (pinfunction "5_5") (pintype "passive"))
      (node (ref "H3") (pin "5") (pinfunction "5_5") (pintype "passive"))
      (node (ref "H4") (pin "5") (pinfunction "5_5") (pintype "passive"))
      (node (ref "H5") (pin "5") (pinfunction "5_5") (pintype "passive"))
      (node (ref "H6") (pin "5") (pinfunction "5_5") (pintype "passive"))
      (node (ref "L3") (pin "2") (pinfunction "K_2") (pintype "passive"))
      (node (ref "P1") (pin "1") (pinfunction "1_1") (pintype "passive"))
      (node (ref "PS1") (pin "2") (pinfunction "GND_2") (pintype "passive"))
      (node (ref "U10") (pin "5") (pinfunction "GND_5") (pintype "bidirectional"))
      (node (ref "U13") (pin "5") (pinfunction "GND_5") (pintype "bidirectional"))
      (node (ref "U14") (pin "5") (pinfunction "GND_5") (pintype "bidirectional"))
      (node (ref "U15") (pin "5") (pinfunction "GND_5") (pintype "bidirectional"))
      (node (ref "U16") (pin "5") (pinfunction "GND_5") (pintype "bidirectional"))
      (node (ref "U17") (pin "5") (pinfunction "GND_5") (pintype "bidirectional"))
      (node (ref "U18") (pin "5") (pinfunction "GND_5") (pintype "bidirectional"))
      (node (ref "U3") (pin "3") (pinfunction "GND_3") (pintype "power_in"))
      (node (ref "U3") (pin "5") (pinfunction "~{ON}/OFF_5") (pintype "input"))
      (node (ref "U3") (pin "6") (pinfunction "GND_6") (pintype "passive"))
      (node (ref "U4") (pin "5") (pinfunction "GND_5") (pintype "bidirectional"))
      (node (ref "U5") (pin "5") (pinfunction "GND_5") (pintype "bidirectional"))
      (node (ref "U9") (pin "5") (pinfunction "GND_5") (pintype "bidirectional"))
    )
    (net (code "59") (name "GND") (class "Default")
      (node (ref "AMS1") (pin "1") (pinfunction "GND_1") (pintype "passive"))
      (node (ref "BT1") (pin "2") (pinfunction "2_2") (pintype "passive"))
      (node (ref "C1") (pin "2") (pinfunction "2_2") (pintype "passive"))
      (node (ref "C11") (pin "2") (pinfunction "2_2") (pintype "passive"))
      (node (ref "C12") (pin "2") (pinfunction "2_2") (pintype "passive"))
      (node (ref "C13") (pin "2") (pinfunction "2_2") (pintype "passive"))
      (node (ref "C14") (pin "2") (pinfunction "2_2") (pintype "passive"))
      (node (ref "C15") (pin "2") (pinfunction "2_2") (pintype "passive"))
      (node (ref "C16") (pin "1") (pinfunction "1_1") (pintype "passive"))
      (node (ref "C2") (pin "2") (pinfunction "2_2") (pintype "passive"))
      (node (ref "C3") (pin "2") (pinfunction "2_2") (pintype "passive"))
      (node (ref "C4") (pin "2") (pinfunction "2_2") (pintype "passive"))
      (node (ref "C5") (pin "2") (pinfunction "2_2") (pintype "passive"))
      (node (ref "C6") (pin "2") (pinfunction "2_2") (pintype "passive"))
      (node (ref "C7") (pin "2") (pinfunction "2_2") (pintype "passive"))
      (node (ref "C8") (pin "2") (pinfunction "2_2") (pintype "passive"))
      (node (ref "H1") (pin "1") (pinfunction "1_1") (pintype "passive"))
      (node (ref "JP2") (pin "1") (pinfunction "1_1") (pintype "passive"))
      (node (ref "JP3") (pin "4") (pinfunction "4_4") (pintype "passive"))
      (node (ref "L2") (pin "2") (pinfunction "K_2") (pintype "passive"))
      (node (ref "PS1") (pin "4") (pinfunction "0V_4") (pintype "passive"))
      (node (ref "R1") (pin "2") (pinfunction "2_2") (pintype "passive"))
      (node (ref "U11") (pin "7") (pinfunction "GND_7") (pintype "passive"))
      (node (ref "U12") (pin "7") (pinfunction "GND_7") (pintype "passive"))
      (node (ref "U2") (pin "10") (pinfunction "VSS_2_10") (pintype "power_in"))
      (node (ref "U2") (pin "20") (pinfunction "VSSA/VREF-_20") (pintype "power_in"))
      (node (ref "U2") (pin "27") (pinfunction "VSS_3_27") (pintype "power_in"))
      (node (ref "U2") (pin "49") (pinfunction "VSS_4_49") (pintype "power_in"))
      (node (ref "U2") (pin "74") (pinfunction "VSS_5_74") (pintype "power_in"))
      (node (ref "U2") (pin "99") (pinfunction "VSS_99") (pintype "power_in"))
      (node (ref "U6") (pin "7") (pinfunction "GND_7") (pintype "passive"))
      (node (ref "U7") (pin "7") (pinfunction "GND_7") (pintype "passive"))
      (node (ref "U8") (pin "7") (pinfunction "GND_7") (pintype "passive"))
    )
    (net (code "60") (name "Net-(AMS1-VIN)") (class "Default")
      (node (ref "AMS1") (pin "3") (pinfunction "VIN_3") (pintype "passive"))
      (node (ref "C3") (pin "1") (pinfunction "1_1") (pintype "passive"))
      (node (ref "PS1") (pin "6") (pinfunction "+VO_6") (pintype "passive"))
    )
    (net (code "61") (name "Net-(D1-K)") (class "Default")
      (node (ref "D1") (pin "2") (pinfunction "K_2") (pintype "passive"))
      (node (ref "L1") (pin "1") (pinfunction "1_1") (pintype "passive"))
      (node (ref "U3") (pin "2") (pinfunction "OUT_2") (pintype "power_in"))
    )
    (net (code "62") (name "Net-(L2-A)") (class "Default")
      (node (ref "L2") (pin "1") (pinfunction "A_1") (pintype "passive"))
      (node (ref "R3") (pin "2") (pinfunction "2_2") (pintype "passive"))
    )
    (net (code "63") (name "Net-(L3-A)") (class "Default")
      (node (ref "L3") (pin "1") (pinfunction "A_1") (pintype "passive"))
      (node (ref "R4") (pin "2") (pinfunction "2_2") (pintype "passive"))
    )
    (net (code "64") (name "Net-(L4-A)") (class "Default")
      (node (ref "L4") (pin "1") (pinfunction "A_1") (pintype "passive"))
      (node (ref "R29") (pin "1") (pinfunction "1_1") (pintype "passive"))
    )
    (net (code "65") (name "Net-(L5-A)") (class "Default")
      (node (ref "L5") (pin "1") (pinfunction "A_1") (pintype "passive"))
      (node (ref "R30") (pin "2") (pinfunction "2_2") (pintype "passive"))
    )
    (net (code "66") (name "Net-(U2B-BOOT0)") (class "Default")
      (node (ref "R1") (pin "1") (pinfunction "1_1") (pintype "passive"))
      (node (ref "U2") (pin "94") (pinfunction "BOOT0_94") (pintype "input"))
    )
    (net (code "67") (name "Net-(U2B-PH0-OSC_IN)") (class "Default")
      (node (ref "C1") (pin "1") (pinfunction "1_1") (pintype "passive"))
      (node (ref "U2") (pin "12") (pinfunction "PH0-OSC_IN_12") (pintype "bidirectional"))
      (node (ref "Y1") (pin "2") (pinfunction "2_2") (pintype "passive"))
    )
    (net (code "68") (name "Net-(U2B-PH1)") (class "Default")
      (node (ref "C2") (pin "1") (pinfunction "1_1") (pintype "passive"))
      (node (ref "U2") (pin "13") (pinfunction "PH1_13") (pintype "bidirectional"))
      (node (ref "Y1") (pin "1") (pinfunction "1_1") (pintype "passive"))
    )
    (net (code "69") (name "Net-(U4-C)") (class "Default")
      (node (ref "R10") (pin "2") (pinfunction "2_2") (pintype "passive"))
      (node (ref "U4") (pin "3") (pinfunction "C_3") (pintype "bidirectional"))
    )
    (net (code "70") (name "Net-(U5-C)") (class "Default")
      (node (ref "R11") (pin "2") (pinfunction "2_2") (pintype "passive"))
      (node (ref "U5") (pin "3") (pinfunction "C_3") (pintype "bidirectional"))
    )
    (net (code "71") (name "Net-(U6-1Y)") (class "Default")
      (node (ref "U6") (pin "2") (pinfunction "1Y_2") (pintype "output"))
      (node (ref "U6") (pin "3") (pinfunction "2A_3") (pintype "input"))
    )
    (net (code "72") (name "Net-(U6-3Y)") (class "Default")
      (node (ref "U6") (pin "6") (pinfunction "3Y_6") (pintype "output"))
      (node (ref "U6") (pin "9") (pinfunction "4A_9") (pintype "input"))
    )
    (net (code "73") (name "Net-(U7-1Y)") (class "Default")
      (node (ref "U7") (pin "2") (pinfunction "1Y_2") (pintype "output"))
      (node (ref "U7") (pin "3") (pinfunction "2A_3") (pintype "input"))
    )
    (net (code "74") (name "Net-(U7-3Y)") (class "Default")
      (node (ref "U7") (pin "6") (pinfunction "3Y_6") (pintype "output"))
      (node (ref "U7") (pin "9") (pinfunction "4A_9") (pintype "input"))
    )
    (net (code "75") (name "Net-(U8-1Y)") (class "Default")
      (node (ref "U8") (pin "2") (pinfunction "1Y_2") (pintype "output"))
      (node (ref "U8") (pin "3") (pinfunction "2A_3") (pintype "input"))
    )
    (net (code "76") (name "Net-(U8-3Y)") (class "Default")
      (node (ref "U8") (pin "6") (pinfunction "3Y_6") (pintype "output"))
      (node (ref "U8") (pin "9") (pinfunction "4A_9") (pintype "input"))
    )
    (net (code "77") (name "Net-(U9-C)") (class "Default")
      (node (ref "R17") (pin "2") (pinfunction "2_2") (pintype "passive"))
      (node (ref "U9") (pin "3") (pinfunction "C_3") (pintype "bidirectional"))
    )
    (net (code "78") (name "Net-(U10-C)") (class "Default")
      (node (ref "R18") (pin "2") (pinfunction "2_2") (pintype "passive"))
      (node (ref "U10") (pin "3") (pinfunction "C_3") (pintype "bidirectional"))
    )
    (net (code "79") (name "Net-(U11-1Y)") (class "Default")
      (node (ref "U11") (pin "2") (pinfunction "1Y_2") (pintype "output"))
      (node (ref "U11") (pin "3") (pinfunction "2A_3") (pintype "input"))
    )
    (net (code "80") (name "Net-(U11-3Y)") (class "Default")
      (node (ref "U11") (pin "6") (pinfunction "3Y_6") (pintype "output"))
      (node (ref "U11") (pin "9") (pinfunction "4A_9") (pintype "input"))
    )
    (net (code "81") (name "Net-(U12-1Y)") (class "Default")
      (node (ref "U12") (pin "2") (pinfunction "1Y_2") (pintype "output"))
      (node (ref "U12") (pin "3") (pinfunction "2A_3") (pintype "input"))
    )
    (net (code "82") (name "Net-(U12-3Y)") (class "Default")
      (node (ref "U12") (pin "6") (pinfunction "3Y_6") (pintype "output"))
      (node (ref "U12") (pin "9") (pinfunction "4A_9") (pintype "input"))
    )
    (net (code "83") (name "Net-(U13-C)") (class "Default")
      (node (ref "R25") (pin "2") (pinfunction "2_2") (pintype "passive"))
      (node (ref "U13") (pin "3") (pinfunction "C_3") (pintype "bidirectional"))
    )
    (net (code "84") (name "Net-(U14-C)") (class "Default")
      (node (ref "R26") (pin "2") (pinfunction "2_2") (pintype "passive"))
      (node (ref "U14") (pin "3") (pinfunction "C_3") (pintype "bidirectional"))
    )
    (net (code "85") (name "Net-(U15-C)") (class "Default")
      (node (ref "R31") (pin "2") (pinfunction "2_2") (pintype "passive"))
      (node (ref "U15") (pin "3") (pinfunction "C_3") (pintype "bidirectional"))
    )
    (net (code "86") (name "Net-(U16-C)") (class "Default")
      (node (ref "R32") (pin "2") (pinfunction "2_2") (pintype "passive"))
      (node (ref "U16") (pin "3") (pinfunction "C_3") (pintype "bidirectional"))
    )
    (net (code "87") (name "Net-(U17-C)") (class "Default")
      (node (ref "R35") (pin "2") (pinfunction "2_2") (pintype "passive"))
      (node (ref "U17") (pin "3") (pinfunction "C_3") (pintype "bidirectional"))
    )
    (net (code "88") (name "Net-(U18-C)") (class "Default")
      (node (ref "R36") (pin "2") (pinfunction "2_2") (pintype "passive"))
      (node (ref "U18") (pin "3") (pinfunction "C_3") (pintype "bidirectional"))
    )
    (net (code "89") (name "unconnected-(U2A-PA4-Pad29)") (class "Default")
      (node (ref "U2") (pin "29") (pinfunction "PA4_29") (pintype "bidirectional"))
    )
    (net (code "90") (name "unconnected-(U2A-PA8-Pad67)") (class "Default")
      (node (ref "U2") (pin "67") (pinfunction "PA8_67") (pintype "bidirectional"))
    )
    (net (code "91") (name "unconnected-(U2A-PA11-Pad70)") (class "Default")
      (node (ref "U2") (pin "70") (pinfunction "PA11_70") (pintype "bidirectional"))
    )
    (net (code "92") (name "unconnected-(U2A-PA12-Pad71)") (class "Default")
      (node (ref "U2") (pin "71") (pinfunction "PA12_71") (pintype "bidirectional"))
    )
    (net (code "93") (name "unconnected-(U2A-PA15-Pad77)") (class "Default")
      (node (ref "U2") (pin "77") (pinfunction "PA15_77") (pintype "bidirectional"))
    )
    (net (code "94") (name "unconnected-(U2A-PB0-Pad35)") (class "Default")
      (node (ref "U2") (pin "35") (pinfunction "PB0_35") (pintype "bidirectional"))
    )
    (net (code "95") (name "unconnected-(U2A-PB1-Pad36)") (class "Default")
      (node (ref "U2") (pin "36") (pinfunction "PB1_36") (pintype "bidirectional"))
    )
    (net (code "96") (name "unconnected-(U2A-PB2-Pad37)") (class "Default")
      (node (ref "U2") (pin "37") (pinfunction "PB2_37") (pintype "bidirectional"))
    )
    (net (code "97") (name "unconnected-(U2A-PB4-Pad90)") (class "Default")
      (node (ref "U2") (pin "90") (pinfunction "PB4_90") (pintype "bidirectional"))
    )
    (net (code "98") (name "unconnected-(U2A-PB5-Pad91)") (class "Default")
      (node (ref "U2") (pin "91") (pinfunction "PB5_91") (pintype "bidirectional"))
    )
    (net (code "99") (name "unconnected-(U2A-PB6-Pad92)") (class "Default")
      (node (ref "U2") (pin "92") (pinfunction "PB6_92") (pintype "bidirectional"))
    )
    (net (code "100") (name "unconnected-(U2A-PB7-Pad93)") (class "Default")
      (node (ref "U2") (pin "93") (pinfunction "PB7_93") (pintype "bidirectional"))
    )
    (net (code "101") (name "unconnected-(U2A-PB10-Pad47)") (class "Default")
      (node (ref "U2") (pin "47") (pinfunction "PB10_47") (pintype "bidirectional"))
    )
    (net (code "102") (name "unconnected-(U2A-PB12-Pad51)") (class "Default")
      (node (ref "U2") (pin "51") (pinfunction "PB12_51") (pintype "bidirectional"))
    )
    (net (code "103") (name "unconnected-(U2A-PB13-Pad52)") (class "Default")
      (node (ref "U2") (pin "52") (pinfunction "PB13_52") (pintype "bidirectional"))
    )
    (net (code "104") (name "unconnected-(U2A-PC0-Pad15)") (class "Default")
      (node (ref "U2") (pin "15") (pinfunction "PC0_15") (pintype "bidirectional"))
    )
    (net (code "105") (name "unconnected-(U2A-PC1-Pad16)") (class "Default")
      (node (ref "U2") (pin "16") (pinfunction "PC1_16") (pintype "bidirectional"))
    )
    (net (code "106") (name "unconnected-(U2A-PC2-Pad17)") (class "Default")
      (node (ref "U2") (pin "17") (pinfunction "PC2_17") (pintype "bidirectional"))
    )
    (net (code "107") (name "unconnected-(U2A-PC3-Pad18)") (class "Default")
      (node (ref "U2") (pin "18") (pinfunction "PC3_18") (pintype "bidirectional"))
    )
    (net (code "108") (name "unconnected-(U2A-PC4-Pad33)") (class "Default")
      (node (ref "U2") (pin "33") (pinfunction "PC4_33") (pintype "bidirectional"))
    )
    (net (code "109") (name "unconnected-(U2A-PC5-Pad34)") (class "Default")
      (node (ref "U2") (pin "34") (pinfunction "PC5_34") (pintype "bidirectional"))
    )
    (net (code "110") (name "unconnected-(U2A-PC10-Pad78)") (class "Default")
      (node (ref "U2") (pin "78") (pinfunction "PC10_78") (pintype "bidirectional"))
    )
    (net (code "111") (name "unconnected-(U2A-PC11-Pad79)") (class "Default")
      (node (ref "U2") (pin "79") (pinfunction "PC11_79") (pintype "bidirectional"))
    )
    (net (code "112") (name "unconnected-(U2A-PC14-OSC32_IN-Pad8)") (class "Default")
      (node (ref "U2") (pin "8") (pinfunction "PC14-OSC32_IN_8") (pintype "bidirectional"))
    )
    (net (code "113") (name "unconnected-(U2A-PC15-OSC32_OUT-Pad9)") (class "Default")
      (node (ref "U2") (pin "9") (pinfunction "PC15-OSC32_OUT_9") (pintype "bidirectional"))
    )
    (net (code "114") (name "unconnected-(U2A-PD0-Pad81)") (class "Default")
      (node (ref "U2") (pin "81") (pinfunction "PD0_81") (pintype "bidirectional"))
    )
    (net (code "115") (name "unconnected-(U2A-PD1-Pad82)") (class "Default")
      (node (ref "U2") (pin "82") (pinfunction "PD1_82") (pintype "bidirectional"))
    )
    (net (code "116") (name "unconnected-(U2A-PD2-Pad83)") (class "Default")
      (node (ref "U2") (pin "83") (pinfunction "PD2_83") (pintype "bidirectional"))
    )
    (net (code "117") (name "unconnected-(U2A-PD3-Pad84)") (class "Default")
      (node (ref "U2") (pin "84") (pinfunction "PD3_84") (pintype "bidirectional"))
    )
    (net (code "118") (name "unconnected-(U2A-PD4-Pad85)") (class "Default")
      (node (ref "U2") (pin "85") (pinfunction "PD4_85") (pintype "bidirectional"))
    )
    (net (code "119") (name "unconnected-(U2A-PD5-Pad86)") (class "Default")
      (node (ref "U2") (pin "86") (pinfunction "PD5_86") (pintype "bidirectional"))
    )
    (net (code "120") (name "unconnected-(U2A-PD6-Pad87)") (class "Default")
      (node (ref "U2") (pin "87") (pinfunction "PD6_87") (pintype "bidirectional"))
    )
    (net (code "121") (name "unconnected-(U2A-PD7-Pad88)") (class "Default")
      (node (ref "U2") (pin "88") (pinfunction "PD7_88") (pintype "bidirectional"))
    )
    (net (code "122") (name "unconnected-(U2A-PD8-Pad55)") (class "Default")
      (node (ref "U2") (pin "55") (pinfunction "PD8_55") (pintype "bidirectional"))
    )
    (net (code "123") (name "unconnected-(U2A-PD9-Pad56)") (class "Default")
      (node (ref "U2") (pin "56") (pinfunction "PD9_56") (pintype "bidirectional"))
    )
    (net (code "124") (name "unconnected-(U2A-PD10-Pad57)") (class "Default")
      (node (ref "U2") (pin "57") (pinfunction "PD10_57") (pintype "bidirectional"))
    )
    (net (code "125") (name "unconnected-(U2A-PD11-Pad58)") (class "Default")
      (node (ref "U2") (pin "58") (pinfunction "PD11_58") (pintype "bidirectional"))
    )
    (net (code "126") (name "unconnected-(U2A-PD14-Pad61)") (class "Default")
      (node (ref "U2") (pin "61") (pinfunction "PD14_61") (pintype "bidirectional"))
    )
    (net (code "127") (name "unconnected-(U2A-PD15-Pad62)") (class "Default")
      (node (ref "U2") (pin "62") (pinfunction "PD15_62") (pintype "bidirectional"))
    )
    (net (code "128") (name "unconnected-(U2B-PE0-Pad97)") (class "Default")
      (node (ref "U2") (pin "97") (pinfunction "PE0_97") (pintype "bidirectional"))
    )
    (net (code "129") (name "unconnected-(U2B-PE1-Pad98)") (class "Default")
      (node (ref "U2") (pin "98") (pinfunction "PE1_98") (pintype "bidirectional"))
    )
    (net (code "130") (name "unconnected-(U2B-PE2-Pad1)") (class "Default")
      (node (ref "U2") (pin "1") (pinfunction "PE2_1") (pintype "bidirectional"))
    )
    (net (code "131") (name "unconnected-(U2B-PE3-Pad2)") (class "Default")
      (node (ref "U2") (pin "2") (pinfunction "PE3_2") (pintype "bidirectional"))
    )
    (net (code "132") (name "unconnected-(U2B-PE4-Pad3)") (class "Default")
      (node (ref "U2") (pin "3") (pinfunction "PE4_3") (pintype "bidirectional"))
    )
    (net (code "133") (name "unconnected-(U2B-PE7-Pad38)") (class "Default")
      (node (ref "U2") (pin "38") (pinfunction "PE7_38") (pintype "bidirectional"))
    )
    (net (code "134") (name "unconnected-(U2B-PE8-Pad39)") (class "Default")
      (node (ref "U2") (pin "39") (pinfunction "PE8_39") (pintype "bidirectional"))
    )
    (net (code "135") (name "unconnected-(U2B-PE10-Pad41)") (class "Default")
      (node (ref "U2") (pin "41") (pinfunction "PE10_41") (pintype "bidirectional"))
    )
    (net (code "136") (name "unconnected-(U2B-PE12-Pad43)") (class "Default")
      (node (ref "U2") (pin "43") (pinfunction "PE12_43") (pintype "bidirectional"))
    )
    (net (code "137") (name "unconnected-(U2B-PE13-Pad44)") (class "Default")
      (node (ref "U2") (pin "44") (pinfunction "PE13_44") (pintype "bidirectional"))
    )
    (net (code "138") (name "unconnected-(U2B-PE14-Pad45)") (class "Default")
      (node (ref "U2") (pin "45") (pinfunction "PE14_45") (pintype "bidirectional"))
    )
    (net (code "139") (name "unconnected-(U2B-PE15-Pad46)") (class "Default")
      (node (ref "U2") (pin "46") (pinfunction "PE15_46") (pintype "bidirectional"))
    )
    (net (code "140") (name "unconnected-(U2C-VBAT-Pad6)") (class "Default")
      (node (ref "U2") (pin "6") (pinfunction "VBAT_6") (pintype "power_in"))
    )
    (net (code "141") (name "unconnected-(U6-5A-Pad11)") (class "Default")
      (node (ref "U6") (pin "11") (pinfunction "5A_11") (pintype "input+no_connect"))
    )
    (net (code "142") (name "unconnected-(U6-5Y-Pad10)") (class "Default")
      (node (ref "U6") (pin "10") (pinfunction "5Y_10") (pintype "output"))
    )
    (net (code "143") (name "unconnected-(U6-6A-Pad13)") (class "Default")
      (node (ref "U6") (pin "13") (pinfunction "6A_13") (pintype "input+no_connect"))
    )
    (net (code "144") (name "unconnected-(U6-6Y-Pad12)") (class "Default")
      (node (ref "U6") (pin "12") (pinfunction "6Y_12") (pintype "output"))
    )
    (net (code "145") (name "unconnected-(U7-5A-Pad11)") (class "Default")
      (node (ref "U7") (pin "11") (pinfunction "5A_11") (pintype "input+no_connect"))
    )
    (net (code "146") (name "unconnected-(U7-5Y-Pad10)") (class "Default")
      (node (ref "U7") (pin "10") (pinfunction "5Y_10") (pintype "output"))
    )
    (net (code "147") (name "unconnected-(U7-6A-Pad13)") (class "Default")
      (node (ref "U7") (pin "13") (pinfunction "6A_13") (pintype "input+no_connect"))
    )
    (net (code "148") (name "unconnected-(U7-6Y-Pad12)") (class "Default")
      (node (ref "U7") (pin "12") (pinfunction "6Y_12") (pintype "output"))
    )
    (net (code "149") (name "unconnected-(U8-5A-Pad11)") (class "Default")
      (node (ref "U8") (pin "11") (pinfunction "5A_11") (pintype "input+no_connect"))
    )
    (net (code "150") (name "unconnected-(U8-5Y-Pad10)") (class "Default")
      (node (ref "U8") (pin "10") (pinfunction "5Y_10") (pintype "output"))
    )
    (net (code "151") (name "unconnected-(U8-6A-Pad13)") (class "Default")
      (node (ref "U8") (pin "13") (pinfunction "6A_13") (pintype "input+no_connect"))
    )
    (net (code "152") (name "unconnected-(U8-6Y-Pad12)") (class "Default")
      (node (ref "U8") (pin "12") (pinfunction "6Y_12") (pintype "output"))
    )
    (net (code "153") (name "unconnected-(U11-5A-Pad11)") (class "Default")
      (node (ref "U11") (pin "11") (pinfunction "5A_11") (pintype "input+no_connect"))
    )
    (net (code "154") (name "unconnected-(U11-5Y-Pad10)") (class "Default")
      (node (ref "U11") (pin "10") (pinfunction "5Y_10") (pintype "output"))
    )
    (net (code "155") (name "unconnected-(U11-6A-Pad13)") (class "Default")
      (node (ref "U11") (pin "13") (pinfunction "6A_13") (pintype "input+no_connect"))
    )
    (net (code "156") (name "unconnected-(U11-6Y-Pad12)") (class "Default")
      (node (ref "U11") (pin "12") (pinfunction "6Y_12") (pintype "output"))
    )
    (net (code "157") (name "unconnected-(U12-5A-Pad11)") (class "Default")
      (node (ref "U12") (pin "11") (pinfunction "5A_11") (pintype "input+no_connect"))
    )
    (net (code "158") (name "unconnected-(U12-5Y-Pad10)") (class "Default")
      (node (ref "U12") (pin "10") (pinfunction "5Y_10") (pintype "output"))
    )
    (net (code "159") (name "unconnected-(U12-6A-Pad13)") (class "Default")
      (node (ref "U12") (pin "13") (pinfunction "6A_13") (pintype "input+no_connect"))
    )
    (net (code "160") (name "unconnected-(U12-6Y-Pad12)") (class "Default")
      (node (ref "U12") (pin "12") (pinfunction "6Y_12") (pintype "output"))
    )
  )
)
